# IdealDiode_03-1_0_complete.net
KiCad netlist of a schematic drawn in Altium Designer
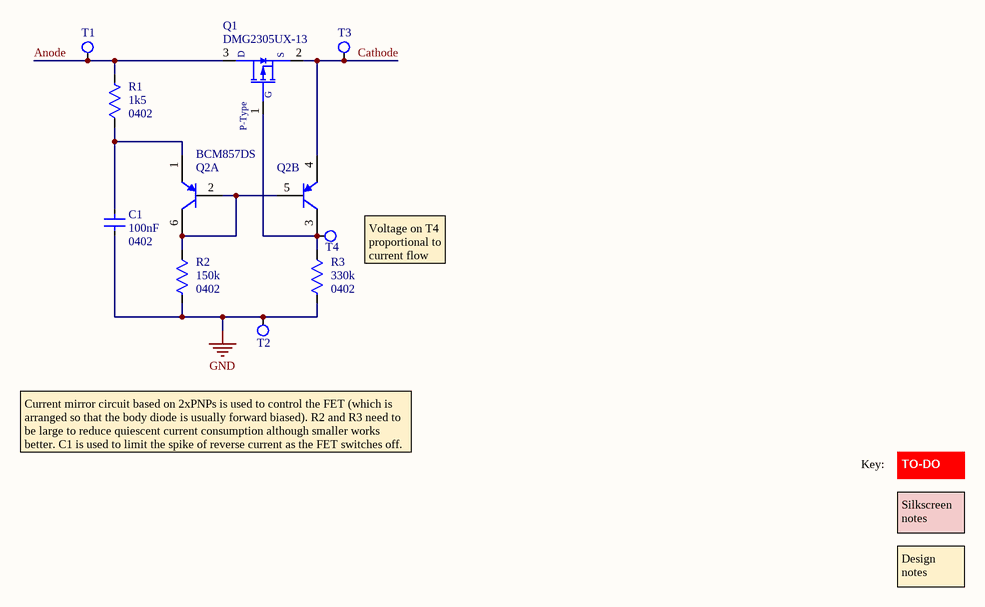
[diagram p0: IdealDiode 03-1.0 complete.SchDoc]

(export (version "E")
  (design (tool "Eeschema 10.0.6"))
  (components
    (comp (ref "C1")
      (value "0402YG104ZAT2A")
      (footprint "CAP0402")
      (description "100nF 0402 16V")
      (fields
        (field (name "MANUFACTURER") "Kyocera AVX")
        (field (name "CASE/PACKAGE") "0402")
        (field (name "TOLERANCE") "80%")
        (field (name "CAPACITANCE") "100nF")
      )
      (libsource (lib "AVX") (part "0402YG104ZAT2A"))
    )
    (comp (ref "Q1")
      (value "MOSFET")
      (footprint "DIODES-SOT23-3")
      (description "MOSFET P-CH 20V 4.2A SOT23")
      (fields (field (name "MANUFACTURER") "Diodes") (field (name "MANUFACTURER PART NUMBER") "DMG2305UX-13"))
      (libsource (lib "DiodesInc") (part "DMG2305UX-whitesch"))
    )
    (comp (ref "Q2")
      (value "BCM857DS")
      (footprint "NXP-SOT457")
      (description "BJT ARRAY, DUAL PNP, -45V, -100MA, 6-SOT-457")
      (fields
        (field (name "MANUFACTURER") "NXP Semiconductors")
        (field (name "MANUFACTURER PART NUMBER") "BCM857DS,115")
      )
      (libsource (lib "NXP") (part "BCM857DS,115-whitesch"))
    )
    (comp (ref "R1")
      (value "1k5")
      (footprint "RES0402")
      (description "Generic 0402 Chip Resistor 1k5")
      (fields (field (name "CASE") "0402"))
      (libsource (lib "generic-res") (part "RES0402_GENERIC"))
    )
    (comp (ref "R2")
      (value "150k")
      (footprint "RES0402")
      (description "Generic 0402 Chip Resistor 150k")
      (fields (field (name "CASE") "0402"))
      (libsource (lib "generic-res") (part "RES0402_GENERIC"))
    )
    (comp (ref "R3")
      (value "330k")
      (footprint "RES0402")
      (description "Generic 0402 Chip Resistor 330k")
      (fields (field (name "CASE") "0402"))
      (libsource (lib "generic-res") (part "RES0402_GENERIC"))
    )
    (comp (ref "T1")
      (value "TestPointHole")
      (footprint "PTH1.5mm-1.0mm")
      (description "Test Point With Hole")
      (libsource (lib "generic") (part "TestPointHole"))
    )
    (comp (ref "T2")
      (value "TestPointHole")
      (footprint "PTH1.5mm-1.0mm")
      (description "Test Point With Hole")
      (libsource (lib "generic") (part "TestPointHole"))
    )
    (comp (ref "T3")
      (value "TestPointHole")
      (footprint "PTH1.5mm-1.0mm")
      (description "Test Point With Hole")
      (libsource (lib "generic") (part "TestPointHole"))
    )
    (comp (ref "T4")
      (value "TestPoint")
      (footprint "Pad1mm")
      (description "Test Point")
      (libsource (lib "generic") (part "TestPoint"))
    )
  )
  (nets
    (net (code "1") (name "/Anode") (class "Default")
      (node (ref "Q1") (pin "3") (pinfunction "D_3") (pintype "passive"))
      (node (ref "R1") (pin "2") (pinfunction "2_2") (pintype "passive"))
      (node (ref "T1") (pin "1") (pinfunction "1_1") (pintype "passive"))
    )
    (net (code "2") (name "/Cathode") (class "Default")
      (node (ref "Q1") (pin "2") (pinfunction "S_2") (pintype "passive"))
      (node (ref "Q2") (pin "4") (pinfunction "E2_4") (pintype "passive"))
      (node (ref "T3") (pin "1") (pinfunction "1_1") (pintype "passive"))
    )
    (net (code "3") (name "GND") (class "Default")
      (node (ref "C1") (pin "1") (pinfunction "1_1") (pintype "passive"))
      (node (ref "R2") (pin "2") (pinfunction "2_2") (pintype "passive"))
      (node (ref "R3") (pin "2") (pinfunction "2_2") (pintype "passive"))
      (node (ref "T2") (pin "1") (pinfunction "1_1") (pintype "passive"))
    )
    (net (code "4") (name "Net-(Q1-G)") (class "Default")
      (node (ref "Q1") (pin "1") (pinfunction "G_1") (pintype "passive"))
      (node (ref "Q2") (pin "3") (pinfunction "C2_3") (pintype "passive"))
      (node (ref "R3") (pin "1") (pinfunction "1_1") (pintype "passive"))
      (node (ref "T4") (pin "1") (pinfunction "1_1") (pintype "passive"))
    )
    (net (code "5") (name "Net-(Q2A-B1)") (class "Default")
      (node (ref "Q2") (pin "2") (pinfunction "B1_2") (pintype "passive"))
      (node (ref "Q2") (pin "5") (pinfunction "B2_5") (pintype "passive"))
      (node (ref "Q2") (pin "6") (pinfunction "C1_6") (pintype "passive"))
      (node (ref "R2") (pin "1") (pinfunction "1_1") (pintype "passive"))
    )
    (net (code "6") (name "Net-(Q2A-E1)") (class "Default")
      (node (ref "C1") (pin "2") (pinfunction "2_2") (pintype "passive"))
      (node (ref "Q2") (pin "1") (pinfunction "E1_1") (pintype "passive"))
      (node (ref "R1") (pin "1") (pinfunction "1_1") (pintype "passive"))
    )
  )
)
